# nycDuino.net
KiCad netlist of a schematic drawn in EAGLE
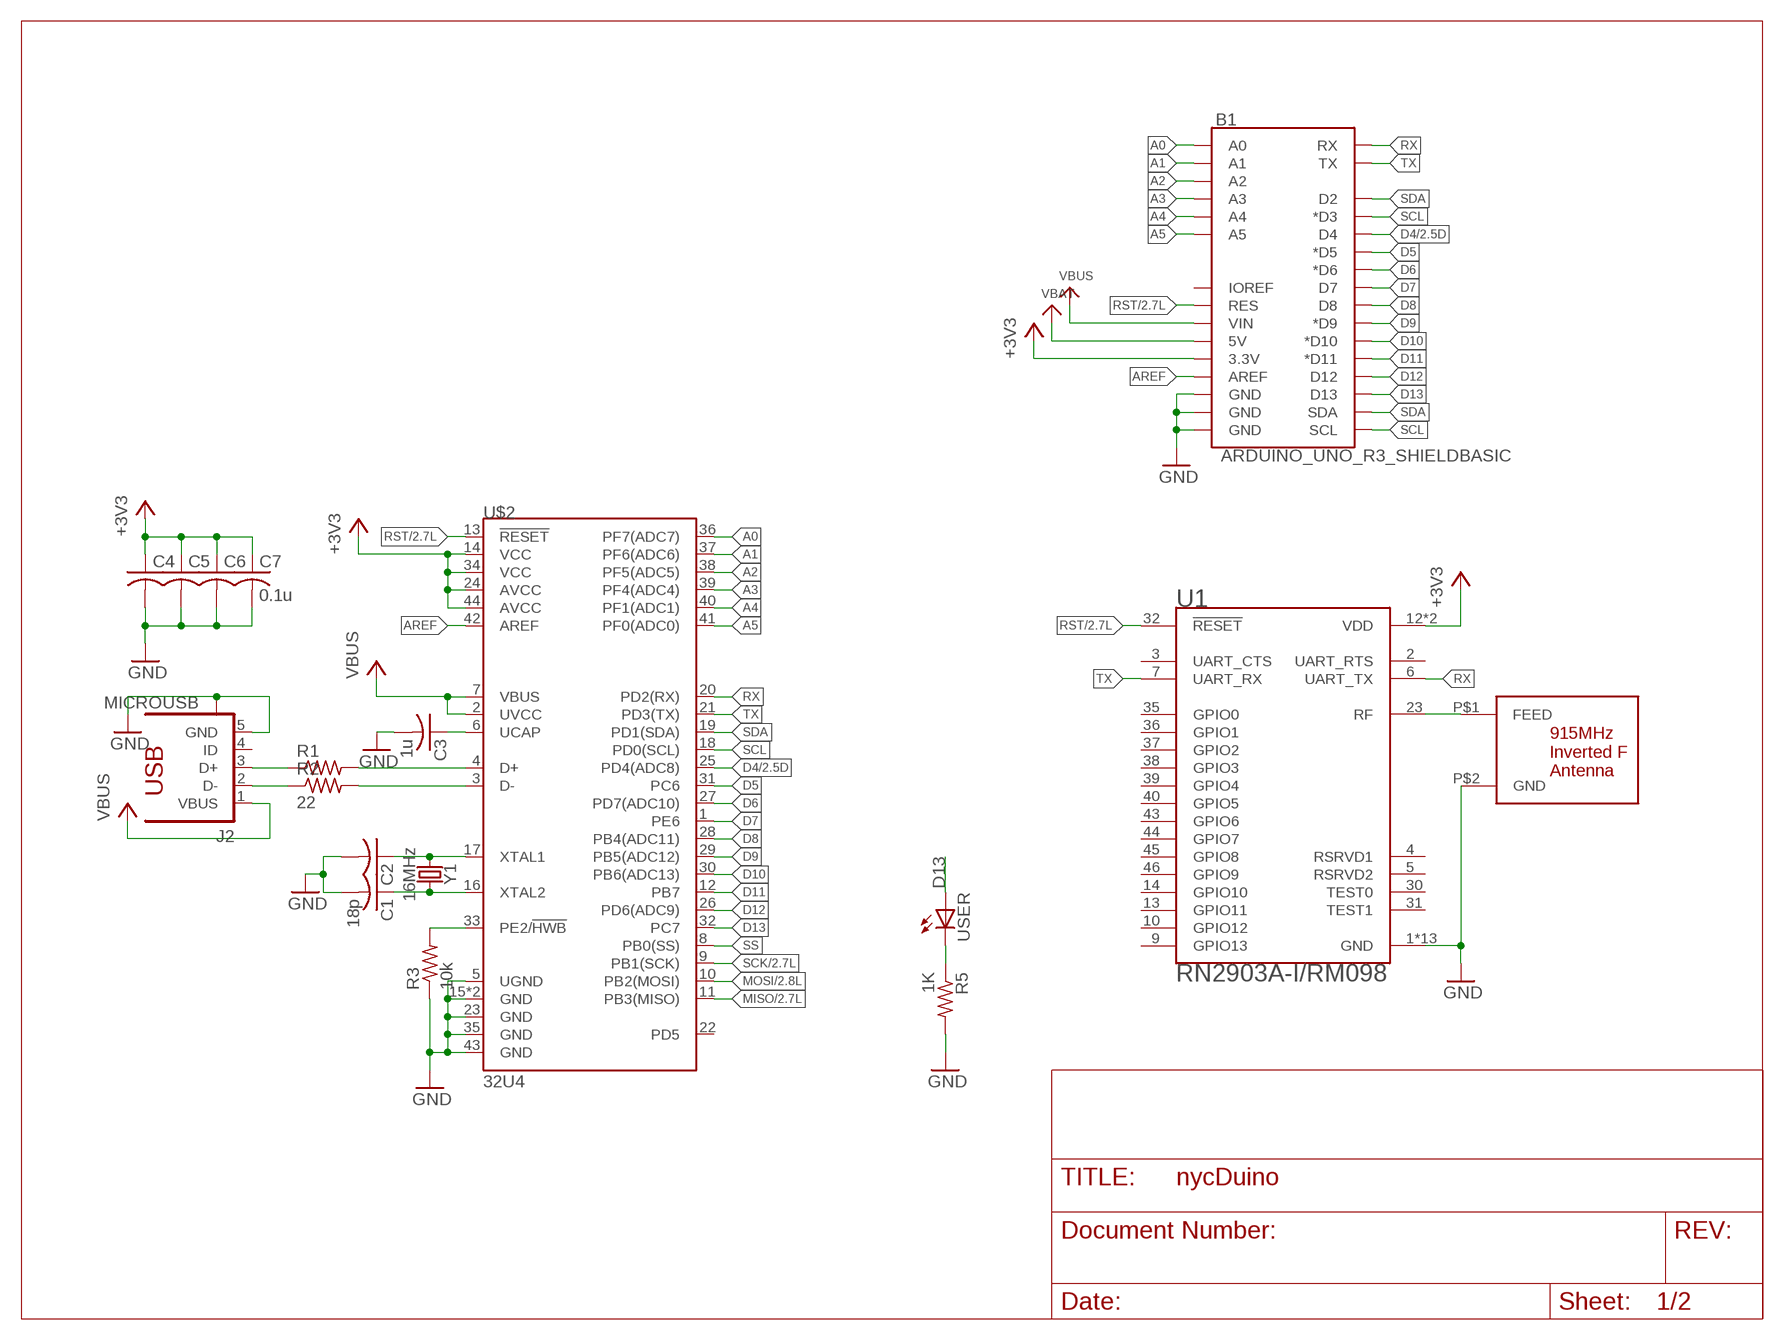
[diagram p0: schematic, sheet 1]
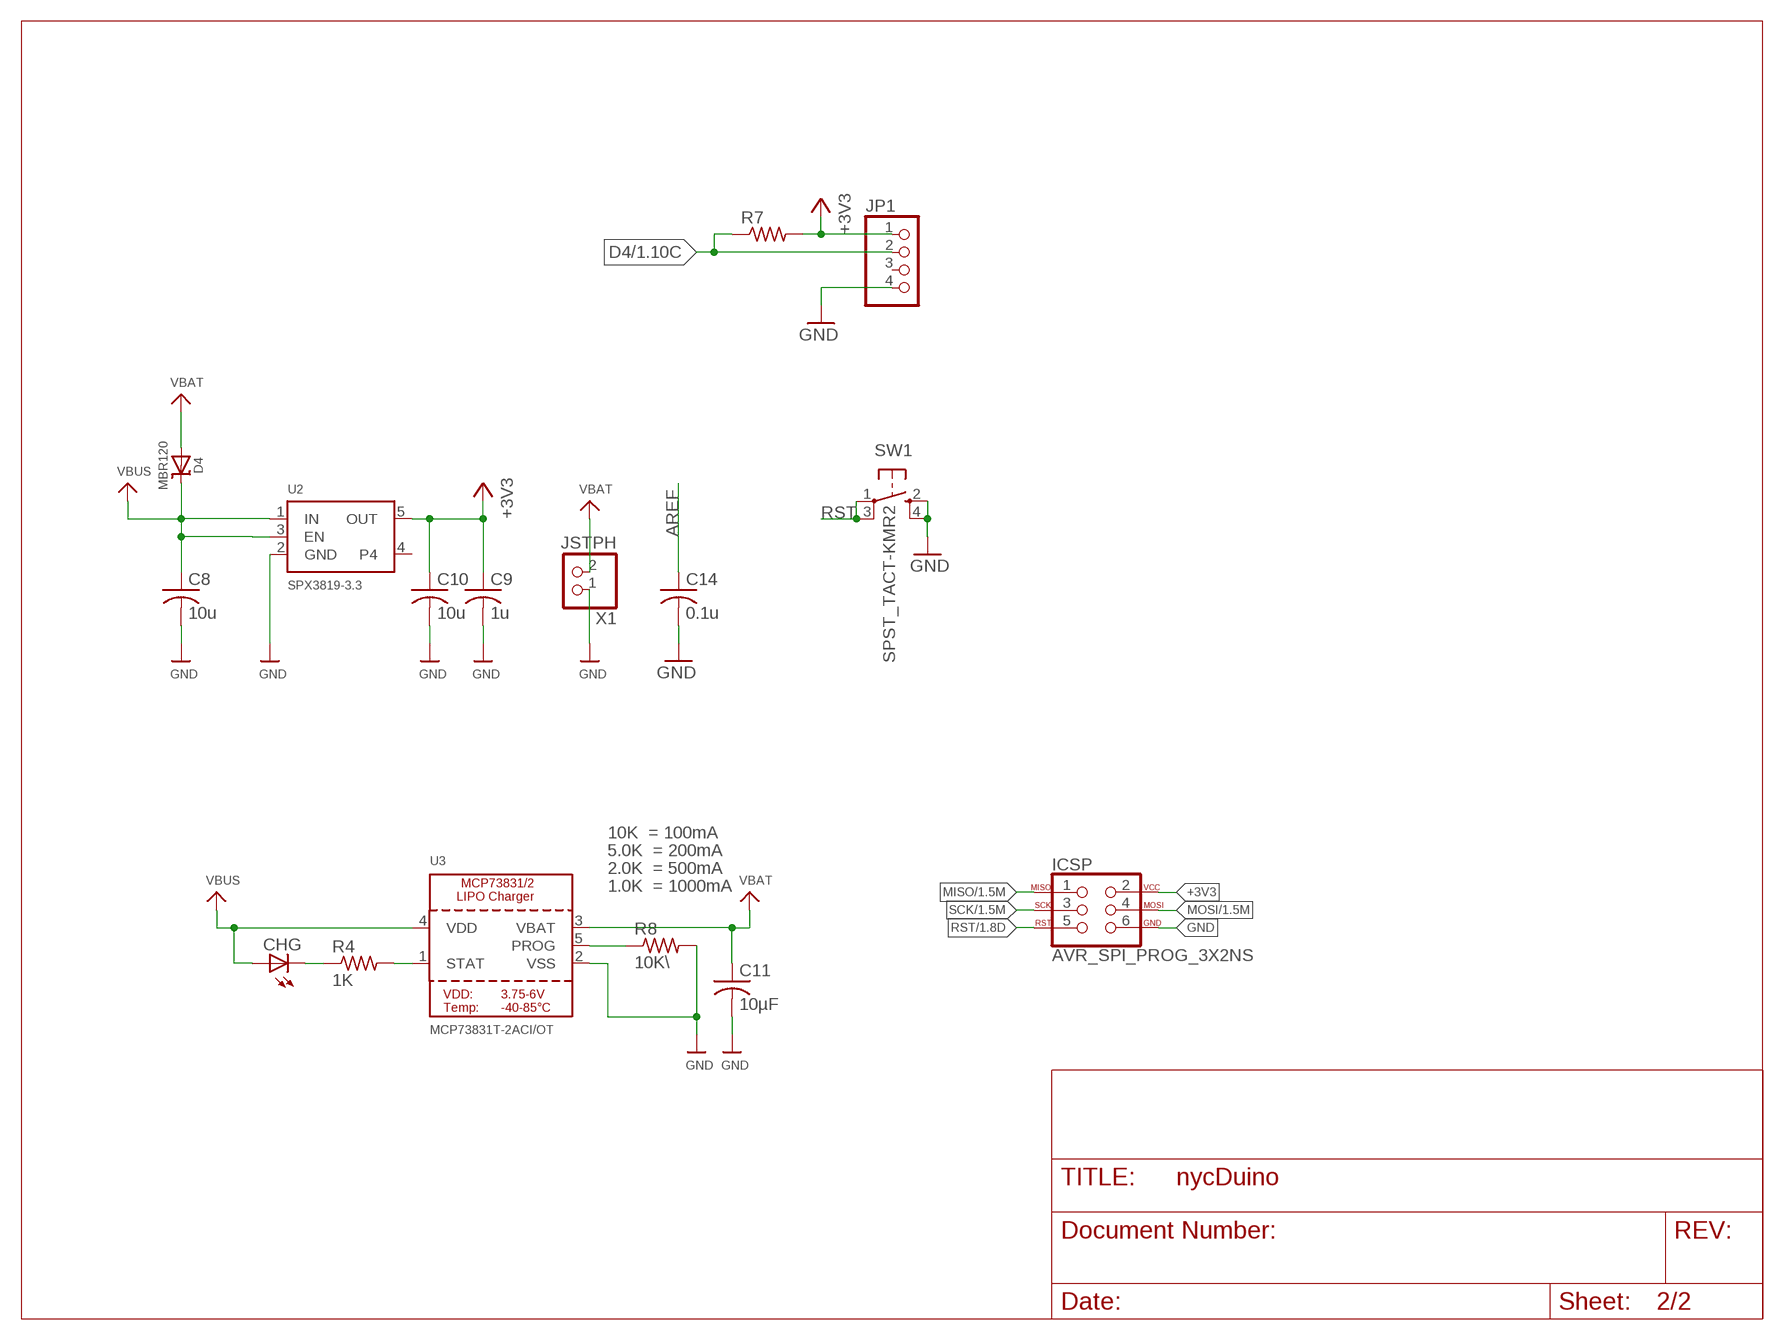
[diagram p1: schematic, sheet 2]

(export (version "E")
  (design (tool "Eeschema 10.0.6"))
  (components
    (comp (ref "B1")
      (value "ARDUINO_UNO_R3_SHIELDBASIC")
      (footprint "eagle-import:UNO_R3_SHIELD")
      (libsource (lib "eagle-import") (part "ARDUINO_UNO_R3_SHIELDBASIC"))
    )
    (comp (ref "C1")
      (value "18p")
      (footprint "eagle-import:C0603")
      (libsource (lib "eagle-import") (part "C-USC0603"))
    )
    (comp (ref "C2")
      (value "C-USC0603")
      (footprint "eagle-import:C0603")
      (libsource (lib "eagle-import") (part "C-USC0603"))
    )
    (comp (ref "C3")
      (value "1u")
      (footprint "eagle-import:C0603")
      (libsource (lib "eagle-import") (part "C-USC0603"))
    )
    (comp (ref "C4")
      (value "C-USC0603")
      (footprint "eagle-import:C0603")
      (libsource (lib "eagle-import") (part "C-USC0603"))
    )
    (comp (ref "C5")
      (value "C-USC0603")
      (footprint "eagle-import:C0603")
      (libsource (lib "eagle-import") (part "C-USC0603"))
    )
    (comp (ref "C6")
      (value "C-USC0603")
      (footprint "eagle-import:C0603")
      (libsource (lib "eagle-import") (part "C-USC0603"))
    )
    (comp (ref "C7")
      (value "0.1u")
      (footprint "eagle-import:C0603")
      (libsource (lib "eagle-import") (part "C-USC0603"))
    )
    (comp (ref "J2")
      (value "MICROUSB")
      (footprint "eagle-import:10118192-0001LF")
      (fields
        (field (name "DIGI-KEY_PART_NUMBER") "609-4613-1-ND")
        (field (name "MF") "Amphenol")
        (field (name "MP") "10118192-0001LF")
      )
      (libsource (lib "eagle-import") (part "MICROUSB"))
    )
    (comp (ref "R1")
      (value "R-US_R0603")
      (footprint "eagle-import:R0603")
      (libsource (lib "eagle-import") (part "R-US_R0603"))
    )
    (comp (ref "R2")
      (value "22")
      (footprint "eagle-import:R0603")
      (libsource (lib "eagle-import") (part "R-US_R0603"))
    )
    (comp (ref "R3")
      (value "10k")
      (footprint "eagle-import:R0603")
      (libsource (lib "eagle-import") (part "R-US_R0603"))
    )
    (comp (ref "R5")
      (value "1K")
      (footprint "eagle-import:R0603")
      (libsource (lib "eagle-import") (part "R-US_R0603"))
    )
    (comp (ref "U$1")
      (value "915MHZ")
      (footprint "eagle-import:915MHZ-F-NOMATCH")
      (libsource (lib "eagle-import") (part "915MHZ"))
    )
    (comp (ref "U$2")
      (value "32U4")
      (footprint "eagle-import:QFN-44")
      (libsource (lib "eagle-import") (part "ATMEGA32U4QFN"))
    )
    (comp (ref "U1")
      (value "RN2903A-I/RM098")
      (footprint "eagle-import:XCVR_RN2903A-I_RM098")
      (fields (field (name "MF") "Microchip"))
      (libsource (lib "eagle-import") (part "RN2903A-I/RM098"))
    )
    (comp (ref "USER")
      (value "LEDCHIP-LED0603")
      (footprint "eagle-import:CHIP-LED0603")
      (libsource (lib "eagle-import") (part "LEDCHIP-LED0603"))
    )
    (comp (ref "Y1")
      (value "16MHz")
      (footprint "eagle-import:CRYSTAL-SMD-5X3.2-4PAD")
      (libsource (lib "eagle-import") (part "CRYSTAL-16MHZSMD-5X3.2"))
    )
    (comp (ref "C8")
      (value "10u")
      (footprint "eagle-import:C0603")
      (libsource (lib "eagle-import") (part "C-USC0603"))
    )
    (comp (ref "C9")
      (value "1u")
      (footprint "eagle-import:C0603")
      (libsource (lib "eagle-import") (part "C-USC0603"))
    )
    (comp (ref "C10")
      (value "10u")
      (footprint "eagle-import:C0603")
      (libsource (lib "eagle-import") (part "C-USC0603"))
    )
    (comp (ref "C11")
      (value "10µF")
      (footprint "eagle-import:C0603")
      (libsource (lib "eagle-import") (part "C-USC0603"))
    )
    (comp (ref "C14")
      (value "0.1u")
      (footprint "eagle-import:C0603")
      (libsource (lib "eagle-import") (part "C-USC0603"))
    )
    (comp (ref "CHG")
      (value "LEDCHIP-LED0603")
      (footprint "eagle-import:CHIP-LED0603")
      (libsource (lib "eagle-import") (part "LEDCHIP-LED0603"))
    )
    (comp (ref "D4")
      (value "MBR120")
      (footprint "eagle-import:SOD-123")
      (libsource (lib "eagle-import") (part "DIODE-SCHOTTKYSOD-123"))
    )
    (comp (ref "ICSP")
      (value "AVR_SPI_PROG_3X2NS")
      (footprint "eagle-import:2X3-NS")
      (libsource (lib "eagle-import") (part "AVR_SPI_PROG_3X2NS"))
    )
    (comp (ref "JP1")
      (value "PINHD-1X4")
      (footprint "eagle-import:1X04")
      (libsource (lib "eagle-import") (part "PINHD-1X4"))
    )
    (comp (ref "R4")
      (value "1K")
      (footprint "eagle-import:R0603")
      (libsource (lib "eagle-import") (part "R-US_R0603"))
    )
    (comp (ref "R7")
      (value "R-US_0207/7")
      (footprint "eagle-import:0207_7")
      (libsource (lib "eagle-import") (part "R-US_0207/7"))
    )
    (comp (ref "R8")
      (value "10K\\")
      (footprint "eagle-import:R0603")
      (libsource (lib "eagle-import") (part "R-US_R0603"))
    )
    (comp (ref "SW1")
      (value "SPST_TACT-KMR2")
      (footprint "eagle-import:KMR2")
      (libsource (lib "eagle-import") (part "SPST_TACT-KMR2"))
    )
    (comp (ref "U2")
      (value "SPX3819-3.3")
      (footprint "eagle-import:SOT23-5")
      (libsource (lib "eagle-import") (part "VREG_SOT23-5"))
    )
    (comp (ref "U3")
      (value "MCP73831T-2ACI/OT")
      (footprint "eagle-import:SOT23-5")
      (libsource (lib "eagle-import") (part "MCP73831/2"))
    )
    (comp (ref "X1")
      (value "JSTPH")
      (footprint "eagle-import:JSTPH2")
      (libsource (lib "eagle-import") (part "CON_JST_PH_2PIN"))
    )
  )
  (nets
    (net (code "1") (name "+3V3") (class "Default")
      (node (ref "B1") (pin "3.3V") (pinfunction "3.3V_3.3V") (pintype "bidirectional"))
      (node (ref "C10") (pin "1") (pinfunction "1_1") (pintype "passive"))
      (node (ref "C4") (pin "1") (pinfunction "1_1") (pintype "passive"))
      (node (ref "C5") (pin "1") (pinfunction "1_1") (pintype "passive"))
      (node (ref "C6") (pin "1") (pinfunction "1_1") (pintype "passive"))
      (node (ref "C7") (pin "1") (pinfunction "1_1") (pintype "passive"))
      (node (ref "C9") (pin "1") (pinfunction "1_1") (pintype "passive"))
      (node (ref "ICSP") (pin "2") (pinfunction "2_2") (pintype "passive"))
      (node (ref "JP1") (pin "1") (pinfunction "1_1") (pintype "passive"))
      (node (ref "R7") (pin "2") (pinfunction "2_2") (pintype "passive"))
      (node (ref "U$2") (pin "14") (pinfunction "VCC_14") (pintype "bidirectional"))
      (node (ref "U$2") (pin "24") (pinfunction "AVCC_24") (pintype "bidirectional"))
      (node (ref "U$2") (pin "34") (pinfunction "VCC_34") (pintype "bidirectional"))
      (node (ref "U$2") (pin "44") (pinfunction "AVCC_44") (pintype "bidirectional"))
      (node (ref "U1") (pin "12") (pinfunction "VDD_12") (pintype "power_in"))
      (node (ref "U1") (pin "34") (pinfunction "VDD_34") (pintype "power_in"))
      (node (ref "U2") (pin "5") (pinfunction "OUT_5") (pintype "power_in"))
    )
    (net (code "2") (name "A0") (class "Default")
      (node (ref "B1") (pin "A0") (pinfunction "A0_A0") (pintype "bidirectional"))
      (node (ref "U$2") (pin "36") (pinfunction "PF7(ADC7)_36") (pintype "bidirectional"))
    )
    (net (code "3") (name "A1") (class "Default")
      (node (ref "B1") (pin "A1") (pinfunction "A1_A1") (pintype "bidirectional"))
      (node (ref "U$2") (pin "37") (pinfunction "PF6(ADC6)_37") (pintype "bidirectional"))
    )
    (net (code "4") (name "A2") (class "Default")
      (node (ref "B1") (pin "A2") (pinfunction "A2_A2") (pintype "bidirectional"))
      (node (ref "U$2") (pin "38") (pinfunction "PF5(ADC5)_38") (pintype "bidirectional"))
    )
    (net (code "5") (name "A3") (class "Default")
      (node (ref "B1") (pin "A3") (pinfunction "A3_A3") (pintype "bidirectional"))
      (node (ref "U$2") (pin "39") (pinfunction "PF4(ADC4)_39") (pintype "bidirectional"))
    )
    (net (code "6") (name "A4") (class "Default")
      (node (ref "B1") (pin "A4") (pinfunction "A4_A4") (pintype "bidirectional"))
      (node (ref "U$2") (pin "40") (pinfunction "PF1(ADC1)_40") (pintype "bidirectional"))
    )
    (net (code "7") (name "A5") (class "Default")
      (node (ref "B1") (pin "A5") (pinfunction "A5_A5") (pintype "bidirectional"))
      (node (ref "U$2") (pin "41") (pinfunction "PF0(ADC0)_41") (pintype "bidirectional"))
    )
    (net (code "8") (name "AREF") (class "Default")
      (node (ref "B1") (pin "AREF") (pinfunction "AREF_AREF") (pintype "bidirectional"))
      (node (ref "C14") (pin "1") (pinfunction "1_1") (pintype "passive"))
      (node (ref "U$2") (pin "42") (pinfunction "AREF_42") (pintype "bidirectional"))
    )
    (net (code "9") (name "D4") (class "Default")
      (node (ref "B1") (pin "D4") (pinfunction "D4_D4") (pintype "bidirectional"))
      (node (ref "JP1") (pin "2") (pinfunction "2_2") (pintype "passive"))
      (node (ref "R7") (pin "1") (pinfunction "1_1") (pintype "passive"))
      (node (ref "U$2") (pin "25") (pinfunction "PD4(ADC8)_25") (pintype "bidirectional"))
    )
    (net (code "10") (name "D5") (class "Default")
      (node (ref "B1") (pin "D5") (pinfunction "*D5_D5") (pintype "bidirectional"))
      (node (ref "U$2") (pin "31") (pinfunction "PC6_31") (pintype "bidirectional"))
    )
    (net (code "11") (name "D6") (class "Default")
      (node (ref "B1") (pin "D6") (pinfunction "*D6_D6") (pintype "bidirectional"))
      (node (ref "U$2") (pin "27") (pinfunction "PD7(ADC10)_27") (pintype "bidirectional"))
    )
    (net (code "12") (name "D7") (class "Default")
      (node (ref "B1") (pin "D7") (pinfunction "D7_D7") (pintype "bidirectional"))
      (node (ref "U$2") (pin "1") (pinfunction "PE6_1") (pintype "bidirectional"))
    )
    (net (code "13") (name "D8") (class "Default")
      (node (ref "B1") (pin "D8") (pinfunction "D8_D8") (pintype "bidirectional"))
      (node (ref "U$2") (pin "28") (pinfunction "PB4(ADC11)_28") (pintype "bidirectional"))
    )
    (net (code "14") (name "D9") (class "Default")
      (node (ref "B1") (pin "D9") (pinfunction "*D9_D9") (pintype "bidirectional"))
      (node (ref "U$2") (pin "29") (pinfunction "PB5(ADC12)_29") (pintype "bidirectional"))
    )
    (net (code "15") (name "D10") (class "Default")
      (node (ref "B1") (pin "D10") (pinfunction "*D10_D10") (pintype "bidirectional"))
      (node (ref "U$2") (pin "30") (pinfunction "PB6(ADC13)_30") (pintype "bidirectional"))
    )
    (net (code "16") (name "D11") (class "Default")
      (node (ref "B1") (pin "D11") (pinfunction "*D11_D11") (pintype "bidirectional"))
      (node (ref "U$2") (pin "12") (pinfunction "PB7_12") (pintype "bidirectional"))
    )
    (net (code "17") (name "D12") (class "Default")
      (node (ref "B1") (pin "D12") (pinfunction "D12_D12") (pintype "bidirectional"))
      (node (ref "U$2") (pin "26") (pinfunction "PD6(ADC9)_26") (pintype "bidirectional"))
    )
    (net (code "18") (name "D13") (class "Default")
      (node (ref "B1") (pin "D13") (pinfunction "D13_D13") (pintype "bidirectional"))
      (node (ref "U$2") (pin "32") (pinfunction "PC7_32") (pintype "bidirectional"))
      (node (ref "USER") (pin "A") (pinfunction "A_A") (pintype "passive"))
    )
    (net (code "19") (name "GND") (class "Default")
      (node (ref "B1") (pin "GND@0") (pinfunction "GND_GND@0") (pintype "bidirectional"))
      (node (ref "B1") (pin "GND@1") (pinfunction "GND_GND@1") (pintype "bidirectional"))
      (node (ref "B1") (pin "GND@2") (pinfunction "GND_GND@2") (pintype "bidirectional"))
      (node (ref "C1") (pin "2") (pinfunction "2_2") (pintype "passive"))
      (node (ref "C10") (pin "2") (pinfunction "2_2") (pintype "passive"))
      (node (ref "C11") (pin "2") (pinfunction "2_2") (pintype "passive"))
      (node (ref "C14") (pin "2") (pinfunction "2_2") (pintype "passive"))
      (node (ref "C2") (pin "2") (pinfunction "2_2") (pintype "passive"))
      (node (ref "C3") (pin "2") (pinfunction "2_2") (pintype "passive"))
      (node (ref "C4") (pin "2") (pinfunction "2_2") (pintype "passive"))
      (node (ref "C5") (pin "2") (pinfunction "2_2") (pintype "passive"))
      (node (ref "C6") (pin "2") (pinfunction "2_2") (pintype "passive"))
      (node (ref "C7") (pin "2") (pinfunction "2_2") (pintype "passive"))
      (node (ref "C8") (pin "2") (pinfunction "2_2") (pintype "passive"))
      (node (ref "C9") (pin "2") (pinfunction "2_2") (pintype "passive"))
      (node (ref "ICSP") (pin "6") (pinfunction "6_6") (pintype "passive"))
      (node (ref "J2") (pin "5") (pinfunction "GND_5") (pintype "passive"))
      (node (ref "J2") (pin "M1") (pinfunction "S_M1") (pintype "passive"))
      (node (ref "J2") (pin "M2") (pinfunction "S_M2") (pintype "passive"))
      (node (ref "J2") (pin "S1") (pinfunction "S_S1") (pintype "passive"))
      (node (ref "J2") (pin "S2") (pinfunction "S_S2") (pintype "passive"))
      (node (ref "J2") (pin "S3") (pinfunction "S_S3") (pintype "passive"))
      (node (ref "J2") (pin "S4") (pinfunction "S_S4") (pintype "passive"))
      (node (ref "JP1") (pin "4") (pinfunction "4_4") (pintype "passive"))
      (node (ref "R3") (pin "1") (pinfunction "1_1") (pintype "passive"))
      (node (ref "R5") (pin "2") (pinfunction "2_2") (pintype "passive"))
      (node (ref "R8") (pin "2") (pinfunction "2_2") (pintype "passive"))
      (node (ref "SW1") (pin "2") (pinfunction "S_2") (pintype "passive"))
      (node (ref "SW1") (pin "4") (pinfunction "S1_4") (pintype "passive"))
      (node (ref "U$1") (pin "P$2") (pinfunction "GND_P$2") (pintype "bidirectional"))
      (node (ref "U$2") (pin "15") (pinfunction "GND_15") (pintype "bidirectional"))
      (node (ref "U$2") (pin "23") (pinfunction "GND_23") (pintype "bidirectional"))
      (node (ref "U$2") (pin "35") (pinfunction "GND_35") (pintype "bidirectional"))
      (node (ref "U$2") (pin "43") (pinfunction "GND_43") (pintype "bidirectional"))
      (node (ref "U$2") (pin "45") (pinfunction "GND_45") (pintype "bidirectional"))
      (node (ref "U$2") (pin "5") (pinfunction "UGND_5") (pintype "bidirectional"))
      (node (ref "U1") (pin "1") (pinfunction "GND_1") (pintype "power_in"))
      (node (ref "U1") (pin "11") (pinfunction "GND_11") (pintype "power_in"))
      (node (ref "U1") (pin "20") (pinfunction "GND_20") (pintype "power_in"))
      (node (ref "U1") (pin "21") (pinfunction "GND_21") (pintype "power_in"))
      (node (ref "U1") (pin "22") (pinfunction "GND_22") (pintype "power_in"))
      (node (ref "U1") (pin "24") (pinfunction "GND_24") (pintype "power_in"))
      (node (ref "U1") (pin "26") (pinfunction "GND_26") (pintype "power_in"))
      (node (ref "U1") (pin "27") (pinfunction "GND_27") (pintype "power_in"))
      (node (ref "U1") (pin "28") (pinfunction "GND_28") (pintype "power_in"))
      (node (ref "U1") (pin "33") (pinfunction "GND_33") (pintype "power_in"))
      (node (ref "U1") (pin "41") (pinfunction "GND_41") (pintype "power_in"))
      (node (ref "U1") (pin "47") (pinfunction "GND_47") (pintype "power_in"))
      (node (ref "U1") (pin "8") (pinfunction "GND_8") (pintype "power_in"))
      (node (ref "U2") (pin "2") (pinfunction "GND_2") (pintype "power_in"))
      (node (ref "U3") (pin "2") (pinfunction "VSS_2") (pintype "power_in"))
      (node (ref "X1") (pin "1") (pinfunction "1_1") (pintype "passive"))
    )
    (net (code "20") (name "MISO") (class "Default")
      (node (ref "ICSP") (pin "1") (pinfunction "1_1") (pintype "passive"))
      (node (ref "U$2") (pin "11") (pinfunction "PB3(MISO)_11") (pintype "bidirectional"))
    )
    (net (code "21") (name "MOSI") (class "Default")
      (node (ref "ICSP") (pin "4") (pinfunction "4_4") (pintype "passive"))
      (node (ref "U$2") (pin "10") (pinfunction "PB2(MOSI)_10") (pintype "bidirectional"))
    )
    (net (code "22") (name "Net-(CHG-PadC)") (class "Default")
      (node (ref "CHG") (pin "C") (pinfunction "C_C") (pintype "passive"))
      (node (ref "R4") (pin "1") (pinfunction "1_1") (pintype "passive"))
    )
    (net (code "23") (name "Net-(J2-D+)") (class "Default")
      (node (ref "J2") (pin "3") (pinfunction "D+_3") (pintype "passive"))
      (node (ref "R1") (pin "1") (pinfunction "1_1") (pintype "passive"))
    )
    (net (code "24") (name "Net-(J2-D-)") (class "Default")
      (node (ref "J2") (pin "2") (pinfunction "D-_2") (pintype "passive"))
      (node (ref "R2") (pin "1") (pinfunction "1_1") (pintype "passive"))
    )
    (net (code "25") (name "Net-(R5-Pad1)") (class "Default")
      (node (ref "R5") (pin "1") (pinfunction "1_1") (pintype "passive"))
      (node (ref "USER") (pin "C") (pinfunction "C_C") (pintype "passive"))
    )
    (net (code "26") (name "Net-(U$1-FEED)") (class "Default")
      (node (ref "U$1") (pin "P$1") (pinfunction "FEED_P$1") (pintype "bidirectional"))
      (node (ref "U1") (pin "23") (pinfunction "RF_23") (pintype "passive"))
    )
    (net (code "27") (name "Net-(U$2-D+)") (class "Default")
      (node (ref "R1") (pin "2") (pinfunction "2_2") (pintype "passive"))
      (node (ref "U$2") (pin "4") (pinfunction "D+_4") (pintype "bidirectional"))
    )
    (net (code "28") (name "Net-(U$2-D-)") (class "Default")
      (node (ref "R2") (pin "2") (pinfunction "2_2") (pintype "passive"))
      (node (ref "U$2") (pin "3") (pinfunction "D-_3") (pintype "bidirectional"))
    )
    (net (code "29") (name "Net-(U$2-PE2{slash}~{HWB})") (class "Default")
      (node (ref "R3") (pin "2") (pinfunction "2_2") (pintype "passive"))
      (node (ref "U$2") (pin "33") (pinfunction "PE2/~{HWB}_33") (pintype "bidirectional"))
    )
    (net (code "30") (name "Net-(U$2-UCAP)") (class "Default")
      (node (ref "C3") (pin "1") (pinfunction "1_1") (pintype "passive"))
      (node (ref "U$2") (pin "6") (pinfunction "UCAP_6") (pintype "bidirectional"))
    )
    (net (code "31") (name "Net-(U$2-XTAL1)") (class "Default")
      (node (ref "C2") (pin "1") (pinfunction "1_1") (pintype "passive"))
      (node (ref "U$2") (pin "17") (pinfunction "XTAL1_17") (pintype "bidirectional"))
      (node (ref "Y1") (pin "1") (pinfunction "1_1") (pintype "passive"))
    )
    (net (code "32") (name "Net-(U$2-XTAL2)") (class "Default")
      (node (ref "C1") (pin "1") (pinfunction "1_1") (pintype "passive"))
      (node (ref "U$2") (pin "16") (pinfunction "XTAL2_16") (pintype "bidirectional"))
      (node (ref "Y1") (pin "3") (pinfunction "2_3") (pintype "passive"))
    )
    (net (code "33") (name "Net-(U3-PROG)") (class "Default")
      (node (ref "R8") (pin "1") (pinfunction "1_1") (pintype "passive"))
      (node (ref "U3") (pin "5") (pinfunction "PROG_5") (pintype "input"))
    )
    (net (code "34") (name "Net-(U3-STAT)") (class "Default")
      (node (ref "R4") (pin "2") (pinfunction "2_2") (pintype "passive"))
      (node (ref "U3") (pin "1") (pinfunction "STAT_1") (pintype "output"))
    )
    (net (code "35") (name "RST") (class "Default")
      (node (ref "B1") (pin "RES") (pinfunction "RES_RES") (pintype "bidirectional"))
      (node (ref "ICSP") (pin "5") (pinfunction "5_5") (pintype "passive"))
      (node (ref "SW1") (pin "1") (pinfunction "P_1") (pintype "passive"))
      (node (ref "SW1") (pin "3") (pinfunction "P1_3") (pintype "passive"))
      (node (ref "U$2") (pin "13") (pinfunction "~{RESET}_13") (pintype "bidirectional"))
      (node (ref "U1") (pin "32") (pinfunction "~{RESET}_32") (pintype "input"))
    )
    (net (code "36") (name "RX") (class "Default")
      (node (ref "B1") (pin "RX") (pinfunction "RX_RX") (pintype "bidirectional"))
      (node (ref "U$2") (pin "20") (pinfunction "PD2(RX)_20") (pintype "bidirectional"))
      (node (ref "U1") (pin "6") (pinfunction "UART_TX_6") (pintype "output"))
    )
    (net (code "37") (name "SCK") (class "Default")
      (node (ref "ICSP") (pin "3") (pinfunction "3_3") (pintype "passive"))
      (node (ref "U$2") (pin "9") (pinfunction "PB1(SCK)_9") (pintype "bidirectional"))
    )
    (net (code "38") (name "SCL") (class "Default")
      (node (ref "B1") (pin "D3") (pinfunction "*D3_D3") (pintype "bidirectional"))
      (node (ref "B1") (pin "SCL") (pinfunction "SCL_SCL") (pintype "bidirectional"))
      (node (ref "U$2") (pin "18") (pinfunction "PD0(SCL)_18") (pintype "bidirectional"))
    )
    (net (code "39") (name "SDA") (class "Default")
      (node (ref "B1") (pin "D2") (pinfunction "D2_D2") (pintype "bidirectional"))
      (node (ref "B1") (pin "SDA") (pinfunction "SDA_SDA") (pintype "bidirectional"))
      (node (ref "U$2") (pin "19") (pinfunction "PD1(SDA)_19") (pintype "bidirectional"))
    )
    (net (code "40") (name "SS") (class "Default")
      (node (ref "U$2") (pin "8") (pinfunction "PB0(SS)_8") (pintype "bidirectional"))
    )
    (net (code "41") (name "TX") (class "Default")
      (node (ref "B1") (pin "TX") (pinfunction "TX_TX") (pintype "bidirectional"))
      (node (ref "U$2") (pin "21") (pinfunction "PD3(TX)_21") (pintype "bidirectional"))
      (node (ref "U1") (pin "7") (pinfunction "UART_RX_7") (pintype "input"))
    )
    (net (code "42") (name "VBAT") (class "Default")
      (node (ref "B1") (pin "5V") (pinfunction "5V_5V") (pintype "bidirectional"))
      (node (ref "C11") (pin "1") (pinfunction "1_1") (pintype "passive"))
      (node (ref "D4") (pin "A") (pinfunction "A_A") (pintype "passive"))
      (node (ref "U3") (pin "3") (pinfunction "VBAT_3") (pintype "power_in"))
      (node (ref "X1") (pin "2") (pinfunction "2_2") (pintype "passive"))
    )
    (net (code "43") (name "VBUS") (class "Default")
      (node (ref "B1") (pin "VIN") (pinfunction "VIN_VIN") (pintype "bidirectional"))
      (node (ref "C8") (pin "1") (pinfunction "1_1") (pintype "passive"))
      (node (ref "CHG") (pin "A") (pinfunction "A_A") (pintype "passive"))
      (node (ref "D4") (pin "C") (pinfunction "C_C") (pintype "passive"))
      (node (ref "J2") (pin "1") (pinfunction "VBUS_1") (pintype "passive"))
      (node (ref "U$2") (pin "2") (pinfunction "UVCC_2") (pintype "bidirectional"))
      (node (ref "U$2") (pin "7") (pinfunction "VBUS_7") (pintype "bidirectional"))
      (node (ref "U2") (pin "1") (pinfunction "IN_1") (pintype "power_in"))
      (node (ref "U2") (pin "3") (pinfunction "EN_3") (pintype "input"))
      (node (ref "U3") (pin "4") (pinfunction "VDD_4") (pintype "power_in"))
    )
    (net (code "44") (name "unconnected-(B1-PadIOREF)") (class "Default")
      (node (ref "B1") (pin "IOREF") (pinfunction "IOREF_IOREF") (pintype "bidirectional"))
    )
    (net (code "45") (name "unconnected-(J2-ID-Pad4)") (class "Default")
      (node (ref "J2") (pin "4") (pinfunction "ID_4") (pintype "passive"))
    )
    (net (code "46") (name "unconnected-(JP1-Pad3)") (class "Default")
      (node (ref "JP1") (pin "3") (pinfunction "3_3") (pintype "passive"))
    )
    (net (code "47") (name "unconnected-(U$2-PD5-Pad22)") (class "Default")
      (node (ref "U$2") (pin "22") (pinfunction "PD5_22") (pintype "bidirectional"))
    )
    (net (code "48") (name "unconnected-(U1-GPIO0-Pad35)") (class "Default")
      (node (ref "U1") (pin "35") (pinfunction "GPIO0_35") (pintype "bidirectional"))
    )
    (net (code "49") (name "unconnected-(U1-GPIO1-Pad36)") (class "Default")
      (node (ref "U1") (pin "36") (pinfunction "GPIO1_36") (pintype "bidirectional"))
    )
    (net (code "50") (name "unconnected-(U1-GPIO2-Pad37)") (class "Default")
      (node (ref "U1") (pin "37") (pinfunction "GPIO2_37") (pintype "bidirectional"))
    )
    (net (code "51") (name "unconnected-(U1-GPIO3-Pad38)") (class "Default")
      (node (ref "U1") (pin "38") (pinfunction "GPIO3_38") (pintype "bidirectional"))
    )
    (net (code "52") (name "unconnected-(U1-GPIO4-Pad39)") (class "Default")
      (node (ref "U1") (pin "39") (pinfunction "GPIO4_39") (pintype "bidirectional"))
    )
    (net (code "53") (name "unconnected-(U1-GPIO5-Pad40)") (class "Default")
      (node (ref "U1") (pin "40") (pinfunction "GPIO5_40") (pintype "bidirectional"))
    )
    (net (code "54") (name "unconnected-(U1-GPIO6-Pad43)") (class "Default")
      (node (ref "U1") (pin "43") (pinfunction "GPIO6_43") (pintype "bidirectional"))
    )
    (net (code "55") (name "unconnected-(U1-GPIO7-Pad44)") (class "Default")
      (node (ref "U1") (pin "44") (pinfunction "GPIO7_44") (pintype "bidirectional"))
    )
    (net (code "56") (name "unconnected-(U1-GPIO8-Pad45)") (class "Default")
      (node (ref "U1") (pin "45") (pinfunction "GPIO8_45") (pintype "bidirectional"))
    )
    (net (code "57") (name "unconnected-(U1-GPIO9-Pad46)") (class "Default")
      (node (ref "U1") (pin "46") (pinfunction "GPIO9_46") (pintype "bidirectional"))
    )
    (net (code "58") (name "unconnected-(U1-GPIO10-Pad14)") (class "Default")
      (node (ref "U1") (pin "14") (pinfunction "GPIO10_14") (pintype "bidirectional"))
    )
    (net (code "59") (name "unconnected-(U1-GPIO11-Pad13)") (class "Default")
      (node (ref "U1") (pin "13") (pinfunction "GPIO11_13") (pintype "bidirectional"))
    )
    (net (code "60") (name "unconnected-(U1-GPIO12-Pad10)") (class "Default")
      (node (ref "U1") (pin "10") (pinfunction "GPIO12_10") (pintype "bidirectional"))
    )
    (net (code "61") (name "unconnected-(U1-GPIO13-Pad9)") (class "Default")
      (node (ref "U1") (pin "9") (pinfunction "GPIO13_9") (pintype "bidirectional"))
    )
    (net (code "62") (name "unconnected-(U1-RSRVD1-Pad4)") (class "Default")
      (node (ref "U1") (pin "4") (pinfunction "RSRVD1_4") (pintype "passive"))
    )
    (net (code "63") (name "unconnected-(U1-RSRVD2-Pad5)") (class "Default")
      (node (ref "U1") (pin "5") (pinfunction "RSRVD2_5") (pintype "passive"))
    )
    (net (code "64") (name "unconnected-(U1-TEST0-Pad30)") (class "Default")
      (node (ref "U1") (pin "30") (pinfunction "TEST0_30") (pintype "passive"))
    )
    (net (code "65") (name "unconnected-(U1-TEST1-Pad31)") (class "Default")
      (node (ref "U1") (pin "31") (pinfunction "TEST1_31") (pintype "passive"))
    )
    (net (code "66") (name "unconnected-(U1-UART_CTS-Pad3)") (class "Default")
      (node (ref "U1") (pin "3") (pinfunction "UART_CTS_3") (pintype "input"))
    )
    (net (code "67") (name "unconnected-(U1-UART_RTS-Pad2)") (class "Default")
      (node (ref "U1") (pin "2") (pinfunction "UART_RTS_2") (pintype "output"))
    )
    (net (code "68") (name "unconnected-(U2-P4-Pad4)") (class "Default")
      (node (ref "U2") (pin "4") (pinfunction "P4_4") (pintype "bidirectional"))
    )
  )
)
